# ECG_Charger.net
KiCad netlist of a schematic drawn in EAGLE
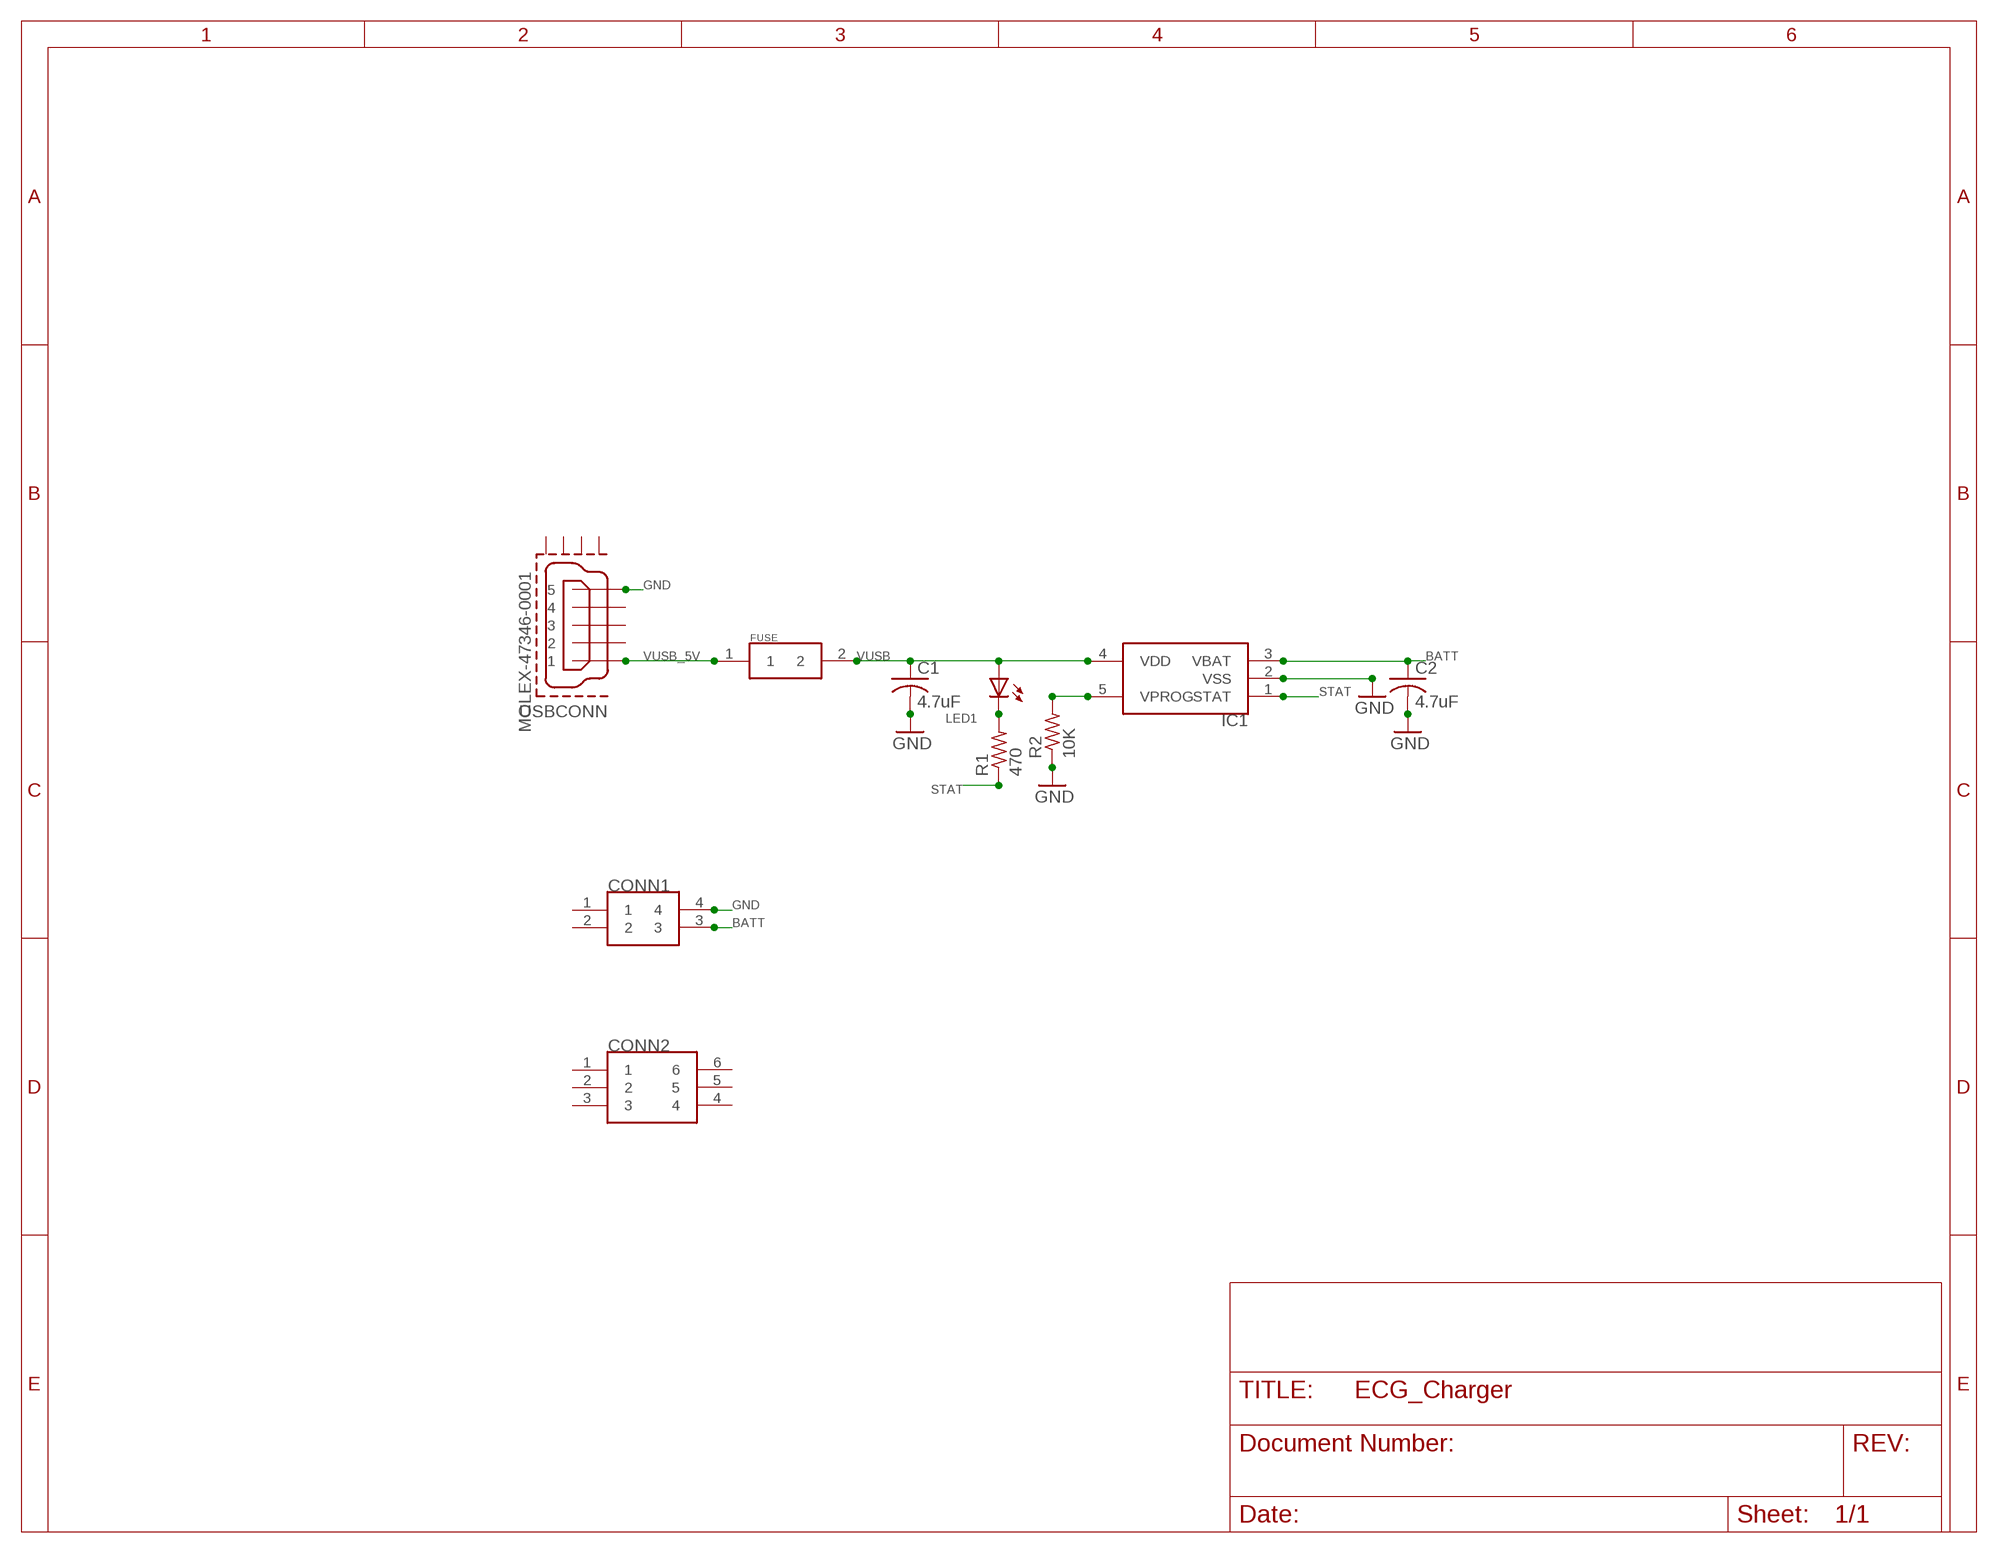
[diagram p0: schematic, sheet 1]

(export (version "E")
  (design (tool "Eeschema 10.0.6"))
  (components
    (comp (ref "C1")
      (value "4.7uF")
      (footprint "eagle-import:C0805")
      (libsource (lib "eagle-import") (part "C-USC0805"))
    )
    (comp (ref "C2")
      (value "4.7uF")
      (footprint "eagle-import:C0805")
      (libsource (lib "eagle-import") (part "C-USC0805"))
    )
    (comp (ref "CONN1")
      (value "M80-4V")
      (footprint "eagle-import:M80-4-V")
      (libsource (lib "eagle-import") (part "M80-4V"))
    )
    (comp (ref "CONN2")
      (value "M80-6V")
      (footprint "eagle-import:M80-6-V")
      (libsource (lib "eagle-import") (part "M80-6V"))
    )
    (comp (ref "FUSE")
      (value "FUSE-MF_SERIES")
      (footprint "eagle-import:1206")
      (libsource (lib "eagle-import") (part "FUSE-MF_SERIES"))
    )
    (comp (ref "IC1")
      (value "MCP73832_SOT23-5")
      (footprint "eagle-import:SOT23-5")
      (libsource (lib "eagle-import") (part "MCP73832_SOT23-5"))
    )
    (comp (ref "LED1")
      (value "LED_SMT_0805")
      (footprint "eagle-import:SMT_LED_0805")
      (libsource (lib "eagle-import") (part "LED_SMT_0805"))
    )
    (comp (ref "R1")
      (value "470")
      (footprint "eagle-import:R0805")
      (libsource (lib "eagle-import") (part "R-US_R0805"))
    )
    (comp (ref "R2")
      (value "10K")
      (footprint "eagle-import:R0805")
      (libsource (lib "eagle-import") (part "R-US_R0805"))
    )
    (comp (ref "USBCONN")
      (value "MOLEX-47346-0001")
      (footprint "eagle-import:MOLEX-47364-0001")
      (libsource (lib "eagle-import") (part "MOLEX-47346-0001"))
    )
  )
  (nets
    (net (code "1") (name "/BATT") (class "Default")
      (node (ref "C2") (pin "1") (pinfunction "1_1") (pintype "passive"))
      (node (ref "CONN1") (pin "3") (pinfunction "3_3") (pintype "bidirectional"))
      (node (ref "IC1") (pin "3") (pinfunction "VBAT_3") (pintype "bidirectional"))
    )
    (net (code "2") (name "/STAT") (class "Default")
      (node (ref "IC1") (pin "1") (pinfunction "STAT_1") (pintype "bidirectional"))
      (node (ref "R1") (pin "1") (pinfunction "1_1") (pintype "passive"))
    )
    (net (code "3") (name "/VUSB") (class "Default")
      (node (ref "C1") (pin "1") (pinfunction "1_1") (pintype "passive"))
      (node (ref "FUSE") (pin "2") (pinfunction "2_2") (pintype "bidirectional"))
      (node (ref "IC1") (pin "4") (pinfunction "VDD_4") (pintype "bidirectional"))
      (node (ref "LED1") (pin "A") (pinfunction "A_A") (pintype "passive"))
    )
    (net (code "4") (name "/VUSB_5V") (class "Default")
      (node (ref "FUSE") (pin "1") (pinfunction "1_1") (pintype "bidirectional"))
      (node (ref "USBCONN") (pin "1") (pinfunction "1_1") (pintype "input"))
    )
    (net (code "5") (name "GND") (class "Default")
      (node (ref "C1") (pin "2") (pinfunction "2_2") (pintype "passive"))
      (node (ref "C2") (pin "2") (pinfunction "2_2") (pintype "passive"))
      (node (ref "CONN1") (pin "4") (pinfunction "4_4") (pintype "bidirectional"))
      (node (ref "IC1") (pin "2") (pinfunction "VSS_2") (pintype "bidirectional"))
      (node (ref "R2") (pin "1") (pinfunction "1_1") (pintype "passive"))
      (node (ref "USBCONN") (pin "5") (pinfunction "5_5") (pintype "input"))
    )
    (net (code "6") (name "Net-(IC1-VPROG)") (class "Default")
      (node (ref "IC1") (pin "5") (pinfunction "VPROG_5") (pintype "bidirectional"))
      (node (ref "R2") (pin "2") (pinfunction "2_2") (pintype "passive"))
    )
    (net (code "7") (name "Net-(LED1-PadC)") (class "Default")
      (node (ref "LED1") (pin "C") (pinfunction "C_C") (pintype "passive"))
      (node (ref "R1") (pin "2") (pinfunction "2_2") (pintype "passive"))
    )
    (net (code "8") (name "unconnected-(CONN1-Pad1)") (class "Default")
      (node (ref "CONN1") (pin "1") (pinfunction "1_1") (pintype "bidirectional"))
    )
    (net (code "9") (name "unconnected-(CONN1-Pad2)") (class "Default")
      (node (ref "CONN1") (pin "2") (pinfunction "2_2") (pintype "bidirectional"))
    )
    (net (code "10") (name "unconnected-(CONN2-Pad1)") (class "Default")
      (node (ref "CONN2") (pin "1") (pinfunction "1_1") (pintype "bidirectional"))
    )
    (net (code "11") (name "unconnected-(CONN2-Pad2)") (class "Default")
      (node (ref "CONN2") (pin "2") (pinfunction "2_2") (pintype "bidirectional"))
    )
    (net (code "12") (name "unconnected-(CONN2-Pad3)") (class "Default")
      (node (ref "CONN2") (pin "3") (pinfunction "3_3") (pintype "bidirectional"))
    )
    (net (code "13") (name "unconnected-(CONN2-Pad4)") (class "Default")
      (node (ref "CONN2") (pin "4") (pinfunction "4_4") (pintype "bidirectional"))
    )
    (net (code "14") (name "unconnected-(CONN2-Pad5)") (class "Default")
      (node (ref "CONN2") (pin "5") (pinfunction "5_5") (pintype "bidirectional"))
    )
    (net (code "15") (name "unconnected-(CONN2-Pad6)") (class "Default")
      (node (ref "CONN2") (pin "6") (pinfunction "6_6") (pintype "bidirectional"))
    )
    (net (code "16") (name "unconnected-(USBCONN-Pad2)") (class "Default")
      (node (ref "USBCONN") (pin "2") (pinfunction "2_2") (pintype "input"))
    )
    (net (code "17") (name "unconnected-(USBCONN-Pad3)") (class "Default")
      (node (ref "USBCONN") (pin "3") (pinfunction "3_3") (pintype "input"))
    )
    (net (code "18") (name "unconnected-(USBCONN-Pad4)") (class "Default")
      (node (ref "USBCONN") (pin "4") (pinfunction "4_4") (pintype "input"))
    )
    (net (code "19") (name "unconnected-(USBCONN-PadGND1)") (class "Default")
      (node (ref "USBCONN") (pin "GND1") (pinfunction "GND1_GND1") (pintype "bidirectional"))
    )
    (net (code "20") (name "unconnected-(USBCONN-PadGND2)") (class "Default")
      (node (ref "USBCONN") (pin "GND2") (pinfunction "GND2_GND2") (pintype "bidirectional"))
    )
    (net (code "21") (name "unconnected-(USBCONN-PadGND3)") (class "Default")
      (node (ref "USBCONN") (pin "GND3") (pinfunction "GND3_GND3") (pintype "bidirectional"))
    )
    (net (code "22") (name "unconnected-(USBCONN-PadGND4)") (class "Default")
      (node (ref "USBCONN") (pin "GND4") (pinfunction "GND4_GND4") (pintype "bidirectional"))
    )
  )
)
